# LedModuleMicrocontroller.net
KiCad netlist of a schematic drawn in Altium Designer
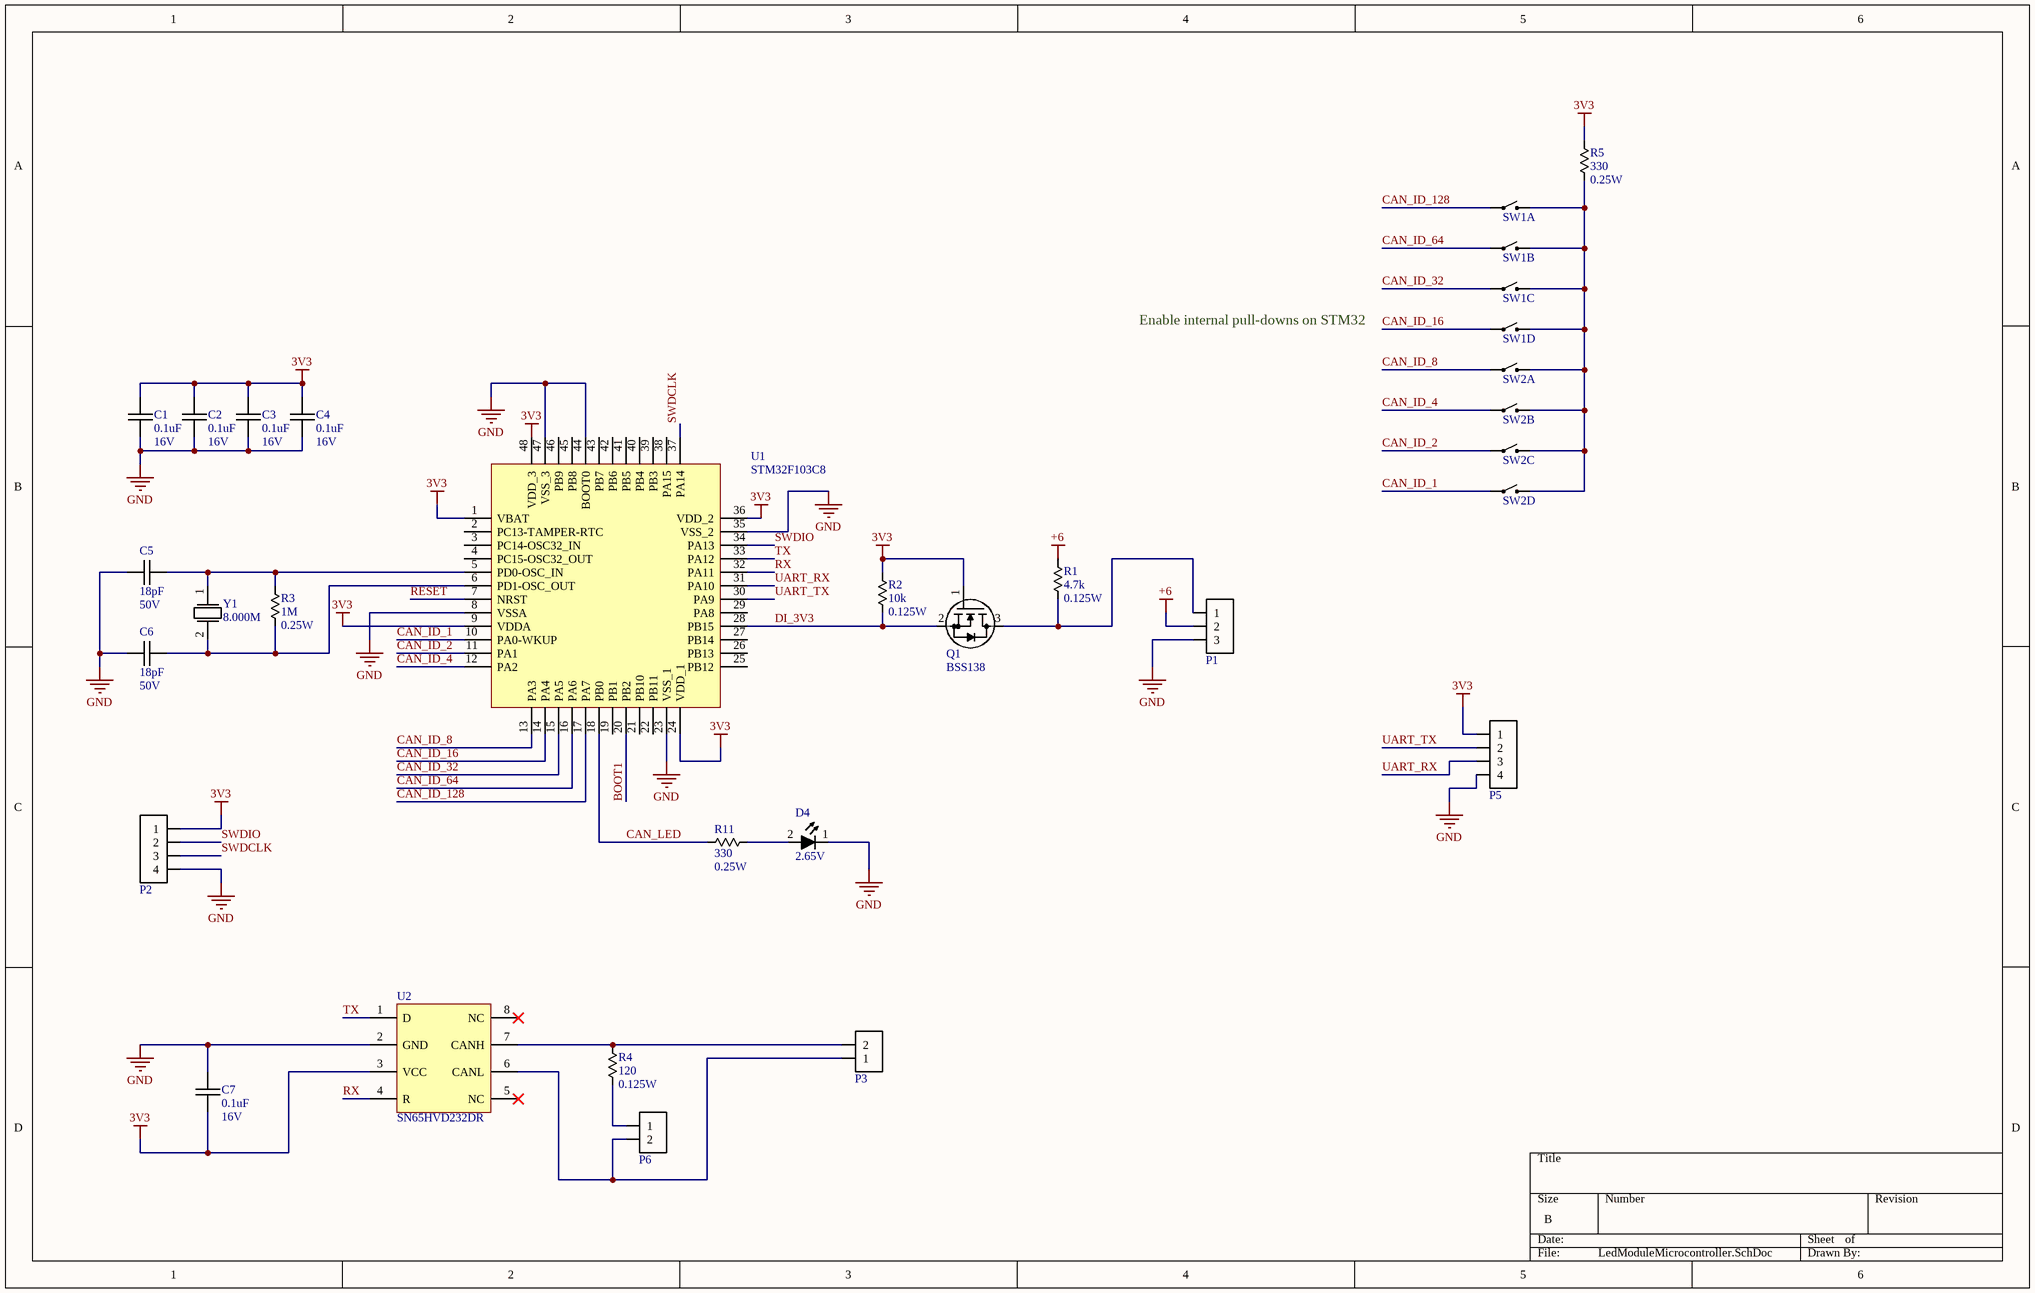
[diagram p0: LedModuleMicrocontroller.SchDoc]

(export (version "E")
  (design (tool "Eeschema 10.0.6"))
  (components
    (comp (ref "C1")
      (value "cap_single_np")
      (footprint "chip_0603")
      (description "CAP, 0.1uF, ±10%, 16V, X7R, 0603")
      (fields
        (field (name "TOLERANCE") "±10%")
        (field (name "CAPACITANCE") "0.1uF")
        (field (name "VOLTAGE RATING") "16V")
        (field (name "PART NUMBER") "CAP-00542")
      )
      (libsource (lib "Capacitors") (part "cap_single_np"))
    )
    (comp (ref "C2")
      (value "cap_single_np")
      (footprint "chip_0603")
      (description "CAP, 0.1uF, ±10%, 16V, X7R, 0603")
      (fields
        (field (name "TOLERANCE") "±10%")
        (field (name "CAPACITANCE") "0.1uF")
        (field (name "VOLTAGE RATING") "16V")
        (field (name "PART NUMBER") "CAP-00542")
      )
      (libsource (lib "Capacitors") (part "cap_single_np"))
    )
    (comp (ref "C3")
      (value "cap_single_np")
      (footprint "chip_0603")
      (description "CAP, 0.1uF, ±10%, 16V, X7R, 0603")
      (fields
        (field (name "TOLERANCE") "±10%")
        (field (name "CAPACITANCE") "0.1uF")
        (field (name "VOLTAGE RATING") "16V")
        (field (name "PART NUMBER") "CAP-00542")
      )
      (libsource (lib "Capacitors") (part "cap_single_np"))
    )
    (comp (ref "C4")
      (value "cap_single_np")
      (footprint "chip_0603")
      (description "CAP, 0.1uF, ±10%, 16V, X7R, 0603")
      (fields
        (field (name "TOLERANCE") "±10%")
        (field (name "CAPACITANCE") "0.1uF")
        (field (name "VOLTAGE RATING") "16V")
        (field (name "PART NUMBER") "CAP-00542")
      )
      (libsource (lib "Capacitors") (part "cap_single_np"))
    )
    (comp (ref "C5")
      (value "cap_single_np")
      (footprint "chip_0603")
      (description "CAP, 18pF, ±2%, 50V, C0G, 0603")
      (fields
        (field (name "TOLERANCE") "±2%")
        (field (name "CAPACITANCE") "18pF")
        (field (name "VOLTAGE RATING") "50V")
        (field (name "PART NUMBER") "CAP-00409")
      )
      (libsource (lib "Capacitors") (part "cap_single_np"))
    )
    (comp (ref "C6")
      (value "cap_single_np")
      (footprint "chip_0603")
      (description "CAP, 18pF, ±2%, 50V, C0G, 0603")
      (fields
        (field (name "TOLERANCE") "±2%")
        (field (name "CAPACITANCE") "18pF")
        (field (name "VOLTAGE RATING") "50V")
        (field (name "PART NUMBER") "CAP-00409")
      )
      (libsource (lib "Capacitors") (part "cap_single_np"))
    )
    (comp (ref "C7")
      (value "cap_single_np")
      (footprint "chip_0603")
      (description "CAP, 0.1uF, ±10%, 16V, X7R, 0603")
      (fields
        (field (name "TOLERANCE") "±10%")
        (field (name "CAPACITANCE") "0.1uF")
        (field (name "VOLTAGE RATING") "16V")
        (field (name "PART NUMBER") "CAP-00542")
      )
      (libsource (lib "Capacitors") (part "cap_single_np"))
    )
    (comp (ref "D4")
      (value "diode_4")
      (footprint "chip_0603")
      (description "LED, Blue, 0603, Low current, HELI2 Series")
      (fields
        (field (name "FORWARD VOLTAGE") "2.65V")
        (field (name "PART NUMBER") "DIO-00049")
        (field (name "MANUFACTURER") "Kingbright")
      )
      (libsource (lib "Diodes") (part "diode_4"))
    )
    (comp (ref "P1")
      (value "conn-3x1_0")
      (footprint "TERM_3.50MM_3x1_0")
      (description "Term Blk, 3 Pos, 16A, 3.5mm Pitch")
      (fields (field (name "PART NUMBER") "CONN-00022") (field (name "MANUFACTURER") "Phoenix Contact"))
      (libsource (lib "Connectors") (part "conn-3x1_0"))
    )
    (comp (ref "P2")
      (value "conn-4x1_0")
      (footprint "HDDR_4x1_0")
      (description "Header 4x1, 0.1\"")
      (fields (field (name "PART NUMBER") "CONN-00029"))
      (libsource (lib "Connectors") (part "conn-4x1_0"))
    )
    (comp (ref "P3")
      (value "conn-2x1_0")
      (footprint "TERM_3.50MM_2x1_0")
      (description "Term Blk, 2 Pos, 16A, 3.5mm Pitch")
      (fields (field (name "PART NUMBER") "CONN-00023") (field (name "MANUFACTURER") "Phoenix Contact"))
      (libsource (lib "Connectors") (part "conn-2x1_0"))
    )
    (comp (ref "P5")
      (value "conn-4x1_0")
      (footprint "HDDR_4x1_0")
      (description "Header 4x1, 0.1\"")
      (fields (field (name "PART NUMBER") "CONN-00029"))
      (libsource (lib "Connectors") (part "conn-4x1_0"))
    )
    (comp (ref "P6")
      (value "conn-2x1_0")
      (footprint "hddr_2x1_0")
      (description "Header, 2x1, 0.1\"")
      (fields (field (name "PART NUMBER") "CONN-00055") (field (name "MANUFACTURER") "Samtec"))
      (libsource (lib "Connectors") (part "conn-2x1_0"))
    )
    (comp (ref "Q1")
      (value "n-mosfet_1")
      (footprint "sot-23-3")
      (description "XSTR NMOS, 220mA, 50V, Vgs 1.3V, SOT-23-3")
      (fields
        (field (name "MANUFACTURER PN") "BSS138")
        (field (name "PART NUMBER") "XSTR-00017")
        (field (name "MANUFACTURER") "ON Semi")
      )
      (libsource (lib "Transistors") (part "n-mosfet_1"))
    )
    (comp (ref "R1")
      (value "res_single")
      (footprint "chip_0805")
      (description "RES SMD 4.7K OHM 1% 1/8W 0805")
      (fields
        (field (name "TOLERANCE") "1%")
        (field (name "RESISTANCE") "4.7k")
        (field (name "POWER RATING") "0.125W")
        (field (name "PART NUMBER") "RES-00471")
      )
      (libsource (lib "Resistors") (part "res_single"))
    )
    (comp (ref "R2")
      (value "res_single")
      (footprint "chip_0805")
      (description "RES SMD 10K OHM 1% 1/8W 0805")
      (fields
        (field (name "TOLERANCE") "1%")
        (field (name "RESISTANCE") "10k")
        (field (name "POWER RATING") "0.125W")
        (field (name "PART NUMBER") "RES-00307")
      )
      (libsource (lib "Resistors") (part "res_single"))
    )
    (comp (ref "R3")
      (value "res_single")
      (footprint "chip_0603")
      (description "RES SMD 1M OHM 1% 1/4W 0603")
      (fields
        (field (name "TOLERANCE") "1%")
        (field (name "RESISTANCE") "1M")
        (field (name "POWER RATING") "0.25W")
        (field (name "PART NUMBER") "RES-00362")
      )
      (libsource (lib "Resistors") (part "res_single"))
    )
    (comp (ref "R4")
      (value "res_single")
      (footprint "chip_0805")
      (description "RES SMD 120 OHM 1% 1/8W 0805")
      (fields
        (field (name "TOLERANCE") "1%")
        (field (name "RESISTANCE") "120")
        (field (name "POWER RATING") "0.125W")
        (field (name "PART NUMBER") "RES-00183")
      )
      (libsource (lib "Resistors") (part "res_single"))
    )
    (comp (ref "R5")
      (value "res_single")
      (footprint "chip_0603")
      (description "RES SMD 330 OHM 1% 1/4W 0603")
      (fields
        (field (name "TOLERANCE") "1%")
        (field (name "RESISTANCE") "330")
        (field (name "POWER RATING") "0.25W")
        (field (name "PART NUMBER") "RES-00221")
      )
      (libsource (lib "Resistors") (part "res_single"))
    )
    (comp (ref "R11")
      (value "res_single")
      (footprint "chip_0603")
      (description "RES SMD 330 OHM 1% 1/4W 0603")
      (fields
        (field (name "TOLERANCE") "1%")
        (field (name "RESISTANCE") "330")
        (field (name "POWER RATING") "0.25W")
        (field (name "PART NUMBER") "RES-00221")
      )
      (libsource (lib "Resistors") (part "res_single"))
    )
    (comp (ref "SW1")
      (value "DIP_SW_4")
      (footprint "A6S-4104-H")
      (description "DIP Switch, SMD, 25mA, 24V")
      (fields (field (name "PART NUMBER") "MISC-00026") (field (name "MANUFACTURER") "Omron"))
      (libsource (lib "Misc") (part "DIP_SW_4"))
    )
    (comp (ref "SW2")
      (value "DIP_SW_4")
      (footprint "A6S-4104-H")
      (description "DIP Switch, SMD, 25mA, 24V")
      (fields (field (name "PART NUMBER") "MISC-00026") (field (name "MANUFACTURER") "Omron"))
      (libsource (lib "Misc") (part "DIP_SW_4"))
    )
    (comp (ref "U1")
      (value "STM32F103C8")
      (footprint "LQFP48_0")
      (description "STM32 M3, LQFP-48")
      (fields
        (field (name "MANUFACTURER PN") "STM32F103C8")
        (field (name "PART NUMBER") "UCTRL-00008")
        (field (name "MANUFACTURER") "ST")
      )
      (libsource (lib "Microcontrollers") (part "STM32F103C8"))
    )
    (comp (ref "U2")
      (value "SN65HVD232")
      (footprint "SO-8")
      (description "CANbus Transceiver, Single channel, SN65HVD232")
      (fields
        (field (name "MANUFACTURER PN") "SN65HVD232DR")
        (field (name "PART NUMBER") "IFACE-00008")
        (field (name "MANUFACTURER") "TI")
      )
      (libsource (lib "Interfaces") (part "SN65HVD232"))
    )
    (comp (ref "Y1")
      (value "osc_xtal_2p_0")
      (footprint "ABLS_AT49_OSC")
      (description "XTAL, 8MHz, 18pF, 20ppm")
      (fields
        (field (name "TOLERANCE") "20ppm")
        (field (name "FREQUENCY") "8.000M")
        (field (name "PART NUMBER") "OSC-00002")
      )
      (libsource (lib "Oscillators") (part "osc_xtal_2p_0"))
    )
  )
  (nets
    (net (code "1") (name "+6") (class "Default")
      (node (ref "P1") (pin "2") (pinfunction "2_2") (pintype "passive"))
      (node (ref "R1") (pin "1") (pinfunction "1_1") (pintype "passive"))
    )
    (net (code "2") (name "/BOOT1") (class "Default")
      (node (ref "U1") (pin "20") (pinfunction "PB2_20") (pintype "passive"))
    )
    (net (code "3") (name "/CAN_ID_1") (class "Default")
      (node (ref "SW2") (pin "4") (pinfunction "4_4") (pintype "passive"))
      (node (ref "U1") (pin "10") (pinfunction "PA0-WKUP_10") (pintype "passive"))
    )
    (net (code "4") (name "/CAN_ID_2") (class "Default")
      (node (ref "SW2") (pin "3") (pinfunction "3_3") (pintype "passive"))
      (node (ref "U1") (pin "11") (pinfunction "PA1_11") (pintype "passive"))
    )
    (net (code "5") (name "/CAN_ID_4") (class "Default")
      (node (ref "SW2") (pin "2") (pinfunction "2_2") (pintype "passive"))
      (node (ref "U1") (pin "12") (pinfunction "PA2_12") (pintype "passive"))
    )
    (net (code "6") (name "/CAN_ID_8") (class "Default")
      (node (ref "SW2") (pin "1") (pinfunction "1_1") (pintype "passive"))
      (node (ref "U1") (pin "13") (pinfunction "PA3_13") (pintype "passive"))
    )
    (net (code "7") (name "/CAN_ID_16") (class "Default")
      (node (ref "SW1") (pin "4") (pinfunction "4_4") (pintype "passive"))
      (node (ref "U1") (pin "14") (pinfunction "PA4_14") (pintype "passive"))
    )
    (net (code "8") (name "/CAN_ID_32") (class "Default")
      (node (ref "SW1") (pin "3") (pinfunction "3_3") (pintype "passive"))
      (node (ref "U1") (pin "15") (pinfunction "PA5_15") (pintype "passive"))
    )
    (net (code "9") (name "/CAN_ID_64") (class "Default")
      (node (ref "SW1") (pin "2") (pinfunction "2_2") (pintype "passive"))
      (node (ref "U1") (pin "16") (pinfunction "PA6_16") (pintype "passive"))
    )
    (net (code "10") (name "/CAN_ID_128") (class "Default")
      (node (ref "SW1") (pin "1") (pinfunction "1_1") (pintype "passive"))
      (node (ref "U1") (pin "17") (pinfunction "PA7_17") (pintype "passive"))
    )
    (net (code "11") (name "/CAN_LED") (class "Default")
      (node (ref "R11") (pin "2") (pinfunction "2_2") (pintype "passive"))
      (node (ref "U1") (pin "18") (pinfunction "PB0_18") (pintype "passive"))
    )
    (net (code "12") (name "/DI_3V3") (class "Default")
      (node (ref "Q1") (pin "2") (pinfunction "S_2") (pintype "passive"))
      (node (ref "R2") (pin "2") (pinfunction "2_2") (pintype "passive"))
      (node (ref "U1") (pin "28") (pinfunction "PB15_28") (pintype "passive"))
    )
    (net (code "13") (name "/RESET") (class "Default")
      (node (ref "U1") (pin "7") (pinfunction "NRST_7") (pintype "passive"))
    )
    (net (code "14") (name "/RX") (class "Default")
      (node (ref "U1") (pin "32") (pinfunction "PA11_32") (pintype "passive"))
      (node (ref "U2") (pin "4") (pinfunction "R_4") (pintype "passive"))
    )
    (net (code "15") (name "/SWDCLK") (class "Default")
      (node (ref "P2") (pin "3") (pinfunction "3_3") (pintype "passive"))
      (node (ref "U1") (pin "37") (pinfunction "PA14_37") (pintype "passive"))
    )
    (net (code "16") (name "/SWDIO") (class "Default")
      (node (ref "P2") (pin "2") (pinfunction "2_2") (pintype "passive"))
      (node (ref "U1") (pin "34") (pinfunction "PA13_34") (pintype "passive"))
    )
    (net (code "17") (name "/TX") (class "Default")
      (node (ref "U1") (pin "33") (pinfunction "PA12_33") (pintype "passive"))
      (node (ref "U2") (pin "1") (pinfunction "D_1") (pintype "passive"))
    )
    (net (code "18") (name "/UART_RX") (class "Default")
      (node (ref "P5") (pin "3") (pinfunction "3_3") (pintype "passive"))
      (node (ref "U1") (pin "31") (pinfunction "PA10_31") (pintype "passive"))
    )
    (net (code "19") (name "/UART_TX") (class "Default")
      (node (ref "P5") (pin "2") (pinfunction "2_2") (pintype "passive"))
      (node (ref "U1") (pin "30") (pinfunction "PA9_30") (pintype "passive"))
    )
    (net (code "20") (name "3V3") (class "Default")
      (node (ref "C1") (pin "1") (pinfunction "1_1") (pintype "passive"))
      (node (ref "C2") (pin "1") (pinfunction "1_1") (pintype "passive"))
      (node (ref "C3") (pin "1") (pinfunction "1_1") (pintype "passive"))
      (node (ref "C4") (pin "1") (pinfunction "1_1") (pintype "passive"))
      (node (ref "C7") (pin "2") (pinfunction "2_2") (pintype "passive"))
      (node (ref "P2") (pin "1") (pinfunction "1_1") (pintype "passive"))
      (node (ref "P5") (pin "1") (pinfunction "1_1") (pintype "passive"))
      (node (ref "Q1") (pin "1") (pinfunction "G_1") (pintype "passive"))
      (node (ref "R2") (pin "1") (pinfunction "1_1") (pintype "passive"))
      (node (ref "R5") (pin "1") (pinfunction "1_1") (pintype "passive"))
      (node (ref "U1") (pin "1") (pinfunction "VBAT_1") (pintype "passive"))
      (node (ref "U1") (pin "24") (pinfunction "VDD_1_24") (pintype "passive"))
      (node (ref "U1") (pin "36") (pinfunction "VDD_2_36") (pintype "passive"))
      (node (ref "U1") (pin "48") (pinfunction "VDD_3_48") (pintype "passive"))
      (node (ref "U1") (pin "9") (pinfunction "VDDA_9") (pintype "passive"))
      (node (ref "U2") (pin "3") (pinfunction "VCC_3") (pintype "passive"))
    )
    (net (code "21") (name "GND") (class "Default")
      (node (ref "C1") (pin "2") (pinfunction "2_2") (pintype "passive"))
      (node (ref "C2") (pin "2") (pinfunction "2_2") (pintype "passive"))
      (node (ref "C3") (pin "2") (pinfunction "2_2") (pintype "passive"))
      (node (ref "C4") (pin "2") (pinfunction "2_2") (pintype "passive"))
      (node (ref "C5") (pin "2") (pinfunction "2_2") (pintype "passive"))
      (node (ref "C6") (pin "1") (pinfunction "1_1") (pintype "passive"))
      (node (ref "C7") (pin "1") (pinfunction "1_1") (pintype "passive"))
      (node (ref "D4") (pin "1") (pinfunction "1_1") (pintype "passive"))
      (node (ref "P1") (pin "3") (pinfunction "3_3") (pintype "passive"))
      (node (ref "P2") (pin "4") (pinfunction "4_4") (pintype "passive"))
      (node (ref "P5") (pin "4") (pinfunction "4_4") (pintype "passive"))
      (node (ref "U1") (pin "23") (pinfunction "VSS_1_23") (pintype "passive"))
      (node (ref "U1") (pin "35") (pinfunction "VSS_2_35") (pintype "passive"))
      (node (ref "U1") (pin "44") (pinfunction "BOOT0_44") (pintype "passive"))
      (node (ref "U1") (pin "47") (pinfunction "VSS_3_47") (pintype "passive"))
      (node (ref "U1") (pin "8") (pinfunction "VSSA_8") (pintype "passive"))
      (node (ref "U2") (pin "2") (pinfunction "GND_2") (pintype "passive"))
    )
    (net (code "22") (name "Net-(D4-Pad2)") (class "Default")
      (node (ref "D4") (pin "2") (pinfunction "2_2") (pintype "passive"))
      (node (ref "R11") (pin "1") (pinfunction "1_1") (pintype "passive"))
    )
    (net (code "23") (name "Net-(P6-Pad1)") (class "Default")
      (node (ref "P6") (pin "1") (pinfunction "1_1") (pintype "passive"))
      (node (ref "R4") (pin "2") (pinfunction "2_2") (pintype "passive"))
    )
    (net (code "24") (name "Net-(Q1-D)") (class "Default")
      (node (ref "P1") (pin "1") (pinfunction "1_1") (pintype "passive"))
      (node (ref "Q1") (pin "3") (pinfunction "D_3") (pintype "passive"))
      (node (ref "R1") (pin "2") (pinfunction "2_2") (pintype "passive"))
    )
    (net (code "25") (name "Net-(R5-Pad2)") (class "Default")
      (node (ref "R5") (pin "2") (pinfunction "2_2") (pintype "passive"))
      (node (ref "SW1") (pin "5") (pinfunction "5_5") (pintype "passive"))
      (node (ref "SW1") (pin "6") (pinfunction "6_6") (pintype "passive"))
      (node (ref "SW1") (pin "7") (pinfunction "7_7") (pintype "passive"))
      (node (ref "SW1") (pin "8") (pinfunction "8_8") (pintype "passive"))
      (node (ref "SW2") (pin "5") (pinfunction "5_5") (pintype "passive"))
      (node (ref "SW2") (pin "6") (pinfunction "6_6") (pintype "passive"))
      (node (ref "SW2") (pin "7") (pinfunction "7_7") (pintype "passive"))
      (node (ref "SW2") (pin "8") (pinfunction "8_8") (pintype "passive"))
    )
    (net (code "26") (name "Net-(U1-PD0-OSC_IN)") (class "Default")
      (node (ref "C5") (pin "1") (pinfunction "1_1") (pintype "passive"))
      (node (ref "R3") (pin "1") (pinfunction "1_1") (pintype "passive"))
      (node (ref "U1") (pin "5") (pinfunction "PD0-OSC_IN_5") (pintype "passive"))
      (node (ref "Y1") (pin "1") (pinfunction "20_1") (pintype "passive"))
    )
    (net (code "27") (name "Net-(U1-PD1-OSC_OUT)") (class "Default")
      (node (ref "C6") (pin "2") (pinfunction "2_2") (pintype "passive"))
      (node (ref "R3") (pin "2") (pinfunction "2_2") (pintype "passive"))
      (node (ref "U1") (pin "6") (pinfunction "PD1-OSC_OUT_6") (pintype "passive"))
      (node (ref "Y1") (pin "2") (pinfunction "20_2") (pintype "passive"))
    )
    (net (code "28") (name "Net-(U2-CANH)") (class "Default")
      (node (ref "P3") (pin "2") (pinfunction "2_2") (pintype "passive"))
      (node (ref "R4") (pin "1") (pinfunction "1_1") (pintype "passive"))
      (node (ref "U2") (pin "7") (pinfunction "CANH_7") (pintype "passive"))
    )
    (net (code "29") (name "Net-(U2-CANL)") (class "Default")
      (node (ref "P3") (pin "1") (pinfunction "1_1") (pintype "passive"))
      (node (ref "P6") (pin "2") (pinfunction "2_2") (pintype "passive"))
      (node (ref "U2") (pin "6") (pinfunction "CANL_6") (pintype "passive"))
    )
    (net (code "30") (name "unconnected-(U1-PA8-Pad29)") (class "Default")
      (node (ref "U1") (pin "29") (pinfunction "PA8_29") (pintype "passive"))
    )
    (net (code "31") (name "unconnected-(U1-PA15-Pad38)") (class "Default")
      (node (ref "U1") (pin "38") (pinfunction "PA15_38") (pintype "passive"))
    )
    (net (code "32") (name "unconnected-(U1-PB1-Pad19)") (class "Default")
      (node (ref "U1") (pin "19") (pinfunction "PB1_19") (pintype "passive"))
    )
    (net (code "33") (name "unconnected-(U1-PB3-Pad39)") (class "Default")
      (node (ref "U1") (pin "39") (pinfunction "PB3_39") (pintype "passive"))
    )
    (net (code "34") (name "unconnected-(U1-PB4-Pad40)") (class "Default")
      (node (ref "U1") (pin "40") (pinfunction "PB4_40") (pintype "passive"))
    )
    (net (code "35") (name "unconnected-(U1-PB5-Pad41)") (class "Default")
      (node (ref "U1") (pin "41") (pinfunction "PB5_41") (pintype "passive"))
    )
    (net (code "36") (name "unconnected-(U1-PB6-Pad42)") (class "Default")
      (node (ref "U1") (pin "42") (pinfunction "PB6_42") (pintype "passive"))
    )
    (net (code "37") (name "unconnected-(U1-PB7-Pad43)") (class "Default")
      (node (ref "U1") (pin "43") (pinfunction "PB7_43") (pintype "passive"))
    )
    (net (code "38") (name "unconnected-(U1-PB8-Pad45)") (class "Default")
      (node (ref "U1") (pin "45") (pinfunction "PB8_45") (pintype "passive"))
    )
    (net (code "39") (name "unconnected-(U1-PB9-Pad46)") (class "Default")
      (node (ref "U1") (pin "46") (pinfunction "PB9_46") (pintype "passive"))
    )
    (net (code "40") (name "unconnected-(U1-PB10-Pad21)") (class "Default")
      (node (ref "U1") (pin "21") (pinfunction "PB10_21") (pintype "passive"))
    )
    (net (code "41") (name "unconnected-(U1-PB11-Pad22)") (class "Default")
      (node (ref "U1") (pin "22") (pinfunction "PB11_22") (pintype "passive"))
    )
    (net (code "42") (name "unconnected-(U1-PB12-Pad25)") (class "Default")
      (node (ref "U1") (pin "25") (pinfunction "PB12_25") (pintype "passive"))
    )
    (net (code "43") (name "unconnected-(U1-PB13-Pad26)") (class "Default")
      (node (ref "U1") (pin "26") (pinfunction "PB13_26") (pintype "passive"))
    )
    (net (code "44") (name "unconnected-(U1-PB14-Pad27)") (class "Default")
      (node (ref "U1") (pin "27") (pinfunction "PB14_27") (pintype "passive"))
    )
    (net (code "45") (name "unconnected-(U1-PC13-TAMPER-RTC-Pad2)") (class "Default")
      (node (ref "U1") (pin "2") (pinfunction "PC13-TAMPER-RTC_2") (pintype "passive"))
    )
    (net (code "46") (name "unconnected-(U1-PC14-OSC32_IN-Pad3)") (class "Default")
      (node (ref "U1") (pin "3") (pinfunction "PC14-OSC32_IN_3") (pintype "passive"))
    )
    (net (code "47") (name "unconnected-(U1-PC15-OSC32_OUT-Pad4)") (class "Default")
      (node (ref "U1") (pin "4") (pinfunction "PC15-OSC32_OUT_4") (pintype "passive"))
    )
    (net (code "48") (name "unconnected-(U2-NC-Pad5)") (class "Default")
      (node (ref "U2") (pin "5") (pinfunction "NC_5") (pintype "passive+no_connect"))
    )
    (net (code "49") (name "unconnected-(U2-NC-Pad8)") (class "Default")
      (node (ref "U2") (pin "8") (pinfunction "NC_8") (pintype "passive+no_connect"))
    )
  )
)
